# schematic.net
KiCad netlist of a schematic drawn in Altium Designer
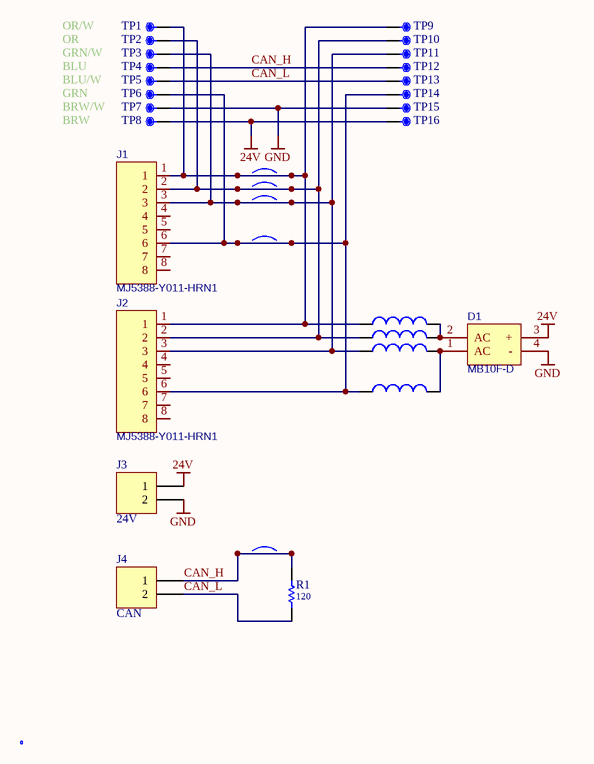
[diagram p0: schematic.SchDoc]

(export (version "E")
  (design (tool "Eeschema 10.0.6"))
  (components
    (comp (ref "D1")
      (value "MB10F-D")
      (footprint "MINIDIP_4P-L4.7-W3.8-P2.50-LS7.0-BL")
      (fields (field (name "LCSC PART NUMBER") "C908753"))
      (libsource (lib "Schlib1") (part "MB10F-D"))
    )
    (comp (ref "J1")
      (value "MJ5388-Y011-HRN1")
      (footprint "RJ45-TH_MJ5388-Y011-HRN1")
      (libsource (lib "Schlib1") (part "MJ88H-B011-HLRV1-1P_C2689153"))
    )
    (comp (ref "J2")
      (value "MJ5388-Y011-HRN1")
      (footprint "RJ45-TH_MJ5388-Y011-HRN1")
      (libsource (lib "Schlib1") (part "MJ88H-B011-HLRV1-1P_C2689153"))
    )
    (comp (ref "J3")
      (value "24V")
      (footprint "CONN_DG308-2.54-2P")
      (description "DG308-2.54-02P-14-00A(H)")
      (fields (field (name "LCSC PART NUMBER") "C699496"))
      (libsource (lib "Miscellaneous Devices") (part "CONN MOLEX HDR-M 1x4"))
    )
    (comp (ref "J4")
      (value "CAN")
      (footprint "CONN_DG308-2.54-2P")
      (description "DG308-2.54-02P-14-00A(H)")
      (fields (field (name "LCSC PART NUMBER") "C699496"))
      (libsource (lib "Miscellaneous Devices") (part "CONN MOLEX HDR-M 1x4"))
    )
    (comp (ref "L1")
      (value "BEAD")
      (footprint "L0603")
      (description "380mΩ ±25% 600Ω@100MHz 0603 Ferrite Beads")
      (fields (field (name "LCSC PART NUMBER") "C19330"))
      (libsource (lib "Miscellaneous Devices") (part "BLM18AG601SN1D"))
    )
    (comp (ref "L2")
      (value "BEAD")
      (footprint "L0603")
      (description "380mΩ ±25% 600Ω@100MHz 0603 Ferrite Beads")
      (fields (field (name "LCSC PART NUMBER") "C19330"))
      (libsource (lib "Miscellaneous Devices") (part "BLM18AG601SN1D"))
    )
    (comp (ref "L3")
      (value "BEAD")
      (footprint "L0603")
      (description "380mΩ ±25% 600Ω@100MHz 0603 Ferrite Beads")
      (fields (field (name "LCSC PART NUMBER") "C19330"))
      (libsource (lib "Miscellaneous Devices") (part "BLM18AG601SN1D"))
    )
    (comp (ref "L4")
      (value "BEAD")
      (footprint "L0603")
      (description "380mΩ ±25% 600Ω@100MHz 0603 Ferrite Beads")
      (fields (field (name "LCSC PART NUMBER") "C19330"))
      (libsource (lib "Miscellaneous Devices") (part "BLM18AG601SN1D"))
    )
    (comp (ref "LOGO1") (value "LOGO") (footprint "LOGO") (libsource (lib "Schlib1") (part "LOGO")))
    (comp (ref "R1")
      (value "120")
      (footprint "R1206")
      (description "120 1206")
      (libsource (lib "Miscellaneous Devices") (part "RES"))
    )
    (comp (ref "SB1")
      (value "Circuit Breaker")
      (footprint "JMP0402_2")
      (libsource (lib "MCD_TOOLS") (part "Circuit Breaker"))
    )
    (comp (ref "SB2")
      (value "Circuit Breaker")
      (footprint "JMP0402_2")
      (libsource (lib "MCD_TOOLS") (part "Circuit Breaker"))
    )
    (comp (ref "SB3")
      (value "Circuit Breaker")
      (footprint "JMP0402_2")
      (libsource (lib "MCD_TOOLS") (part "Circuit Breaker"))
    )
    (comp (ref "SB4")
      (value "Circuit Breaker")
      (footprint "JMP0402_2")
      (libsource (lib "MCD_TOOLS") (part "Circuit Breaker"))
    )
    (comp (ref "SB5")
      (value "Circuit Breaker")
      (footprint "JMP0402_2")
      (libsource (lib "MCD_TOOLS") (part "Circuit Breaker"))
    )
    (comp (ref "TP1")
      (value "~")
      (footprint "TP2030_SMD")
      (libsource (lib "Miscellaneous Devices") (part "TP_Dup1"))
    )
    (comp (ref "TP2")
      (value "~")
      (footprint "TP2030_SMD")
      (libsource (lib "Miscellaneous Devices") (part "TP_Dup1"))
    )
    (comp (ref "TP3")
      (value "~")
      (footprint "TP2030_SMD")
      (libsource (lib "Miscellaneous Devices") (part "TP_Dup1"))
    )
    (comp (ref "TP4")
      (value "~")
      (footprint "TP2030_SMD")
      (libsource (lib "Miscellaneous Devices") (part "TP_Dup1"))
    )
    (comp (ref "TP5")
      (value "~")
      (footprint "TP2030_SMD")
      (libsource (lib "Miscellaneous Devices") (part "TP_Dup1"))
    )
    (comp (ref "TP6")
      (value "~")
      (footprint "TP2030_SMD")
      (libsource (lib "Miscellaneous Devices") (part "TP_Dup1"))
    )
    (comp (ref "TP7")
      (value "~")
      (footprint "TP2030_SMD")
      (libsource (lib "Miscellaneous Devices") (part "TP_Dup1"))
    )
    (comp (ref "TP8")
      (value "~")
      (footprint "TP2030_SMD")
      (libsource (lib "Miscellaneous Devices") (part "TP_Dup1"))
    )
    (comp (ref "TP9")
      (value "~")
      (footprint "TP2030_SMD")
      (libsource (lib "Miscellaneous Devices") (part "TP_Dup1"))
    )
    (comp (ref "TP10")
      (value "~")
      (footprint "TP2030_SMD")
      (libsource (lib "Miscellaneous Devices") (part "TP_Dup1"))
    )
    (comp (ref "TP11")
      (value "~")
      (footprint "TP2030_SMD")
      (libsource (lib "Miscellaneous Devices") (part "TP_Dup1"))
    )
    (comp (ref "TP12")
      (value "~")
      (footprint "TP2030_SMD")
      (libsource (lib "Miscellaneous Devices") (part "TP_Dup1"))
    )
    (comp (ref "TP13")
      (value "~")
      (footprint "TP2030_SMD")
      (libsource (lib "Miscellaneous Devices") (part "TP_Dup1"))
    )
    (comp (ref "TP14")
      (value "~")
      (footprint "TP2030_SMD")
      (libsource (lib "Miscellaneous Devices") (part "TP_Dup1"))
    )
    (comp (ref "TP15")
      (value "~")
      (footprint "TP2030_SMD")
      (libsource (lib "Miscellaneous Devices") (part "TP_Dup1"))
    )
    (comp (ref "TP16")
      (value "~")
      (footprint "TP2030_SMD")
      (libsource (lib "Miscellaneous Devices") (part "TP_Dup1"))
    )
  )
  (nets
    (net (code "1") (name "/CAN_H") (class "Default")
      (node (ref "J4") (pin "1") (pinfunction "1_1") (pintype "passive"))
      (node (ref "R1") (pin "1") (pinfunction "1_1") (pintype "passive"))
      (node (ref "SB5") (pin "1") (pinfunction "1_1") (pintype "passive"))
      (node (ref "SB5") (pin "2") (pinfunction "2_2") (pintype "passive"))
      (node (ref "TP12") (pin "1") (pinfunction "1_1") (pintype "passive"))
      (node (ref "TP4") (pin "1") (pinfunction "1_1") (pintype "passive"))
    )
    (net (code "2") (name "/CAN_L") (class "Default")
      (node (ref "J4") (pin "2") (pinfunction "2_2") (pintype "passive"))
      (node (ref "R1") (pin "2") (pinfunction "2_2") (pintype "passive"))
      (node (ref "TP13") (pin "1") (pinfunction "1_1") (pintype "passive"))
      (node (ref "TP5") (pin "1") (pinfunction "1_1") (pintype "passive"))
    )
    (net (code "3") (name "24V") (class "Default")
      (node (ref "D1") (pin "3") (pinfunction "+_3") (pintype "passive"))
      (node (ref "J3") (pin "1") (pinfunction "1_1") (pintype "passive"))
      (node (ref "TP16") (pin "1") (pinfunction "1_1") (pintype "passive"))
      (node (ref "TP8") (pin "1") (pinfunction "1_1") (pintype "passive"))
    )
    (net (code "4") (name "GND") (class "Default")
      (node (ref "D1") (pin "4") (pinfunction "-_4") (pintype "passive"))
      (node (ref "J3") (pin "2") (pinfunction "2_2") (pintype "passive"))
      (node (ref "TP15") (pin "1") (pinfunction "1_1") (pintype "passive"))
      (node (ref "TP7") (pin "1") (pinfunction "1_1") (pintype "passive"))
    )
    (net (code "5") (name "Net-(D1-AC-Pad1)") (class "Default")
      (node (ref "D1") (pin "1") (pinfunction "AC_1") (pintype "passive"))
      (node (ref "L3") (pin "1") (pinfunction "1_1") (pintype "passive"))
      (node (ref "L4") (pin "1") (pinfunction "1_1") (pintype "passive"))
    )
    (net (code "6") (name "Net-(D1-AC-Pad2)") (class "Default")
      (node (ref "D1") (pin "2") (pinfunction "AC_2") (pintype "passive"))
      (node (ref "L1") (pin "1") (pinfunction "1_1") (pintype "passive"))
      (node (ref "L2") (pin "1") (pinfunction "1_1") (pintype "passive"))
    )
    (net (code "7") (name "Net-(J1-Pad1)") (class "Default")
      (node (ref "J1") (pin "1") (pinfunction "1_1") (pintype "passive"))
      (node (ref "J2") (pin "1") (pinfunction "1_1") (pintype "passive"))
      (node (ref "L1") (pin "2") (pinfunction "2_2") (pintype "passive"))
      (node (ref "SB1") (pin "1") (pinfunction "1_1") (pintype "passive"))
      (node (ref "SB1") (pin "2") (pinfunction "2_2") (pintype "passive"))
      (node (ref "TP1") (pin "1") (pinfunction "1_1") (pintype "passive"))
      (node (ref "TP9") (pin "1") (pinfunction "1_1") (pintype "passive"))
    )
    (net (code "8") (name "Net-(J1-Pad2)") (class "Default")
      (node (ref "J1") (pin "2") (pinfunction "2_2") (pintype "passive"))
      (node (ref "J2") (pin "2") (pinfunction "2_2") (pintype "passive"))
      (node (ref "L2") (pin "2") (pinfunction "2_2") (pintype "passive"))
      (node (ref "SB2") (pin "1") (pinfunction "1_1") (pintype "passive"))
      (node (ref "SB2") (pin "2") (pinfunction "2_2") (pintype "passive"))
      (node (ref "TP10") (pin "1") (pinfunction "1_1") (pintype "passive"))
      (node (ref "TP2") (pin "1") (pinfunction "1_1") (pintype "passive"))
    )
    (net (code "9") (name "Net-(J1-Pad3)") (class "Default")
      (node (ref "J1") (pin "3") (pinfunction "3_3") (pintype "passive"))
      (node (ref "J2") (pin "3") (pinfunction "3_3") (pintype "passive"))
      (node (ref "L3") (pin "2") (pinfunction "2_2") (pintype "passive"))
      (node (ref "SB3") (pin "1") (pinfunction "1_1") (pintype "passive"))
      (node (ref "SB3") (pin "2") (pinfunction "2_2") (pintype "passive"))
      (node (ref "TP11") (pin "1") (pinfunction "1_1") (pintype "passive"))
      (node (ref "TP3") (pin "1") (pinfunction "1_1") (pintype "passive"))
    )
    (net (code "10") (name "Net-(J1-Pad6)") (class "Default")
      (node (ref "J1") (pin "6") (pinfunction "6_6") (pintype "passive"))
      (node (ref "J2") (pin "6") (pinfunction "6_6") (pintype "passive"))
      (node (ref "L4") (pin "2") (pinfunction "2_2") (pintype "passive"))
      (node (ref "SB4") (pin "1") (pinfunction "1_1") (pintype "passive"))
      (node (ref "SB4") (pin "2") (pinfunction "2_2") (pintype "passive"))
      (node (ref "TP14") (pin "1") (pinfunction "1_1") (pintype "passive"))
      (node (ref "TP6") (pin "1") (pinfunction "1_1") (pintype "passive"))
    )
    (net (code "11") (name "unconnected-(J1-Pad4)") (class "Default")
      (node (ref "J1") (pin "4") (pinfunction "4_4") (pintype "passive"))
    )
    (net (code "12") (name "unconnected-(J1-Pad5)") (class "Default")
      (node (ref "J1") (pin "5") (pinfunction "5_5") (pintype "passive"))
    )
    (net (code "13") (name "unconnected-(J1-Pad7)") (class "Default")
      (node (ref "J1") (pin "7") (pinfunction "7_7") (pintype "passive"))
    )
    (net (code "14") (name "unconnected-(J1-Pad8)") (class "Default")
      (node (ref "J1") (pin "8") (pinfunction "8_8") (pintype "passive"))
    )
    (net (code "15") (name "unconnected-(J2-Pad4)") (class "Default")
      (node (ref "J2") (pin "4") (pinfunction "4_4") (pintype "passive"))
    )
    (net (code "16") (name "unconnected-(J2-Pad5)") (class "Default")
      (node (ref "J2") (pin "5") (pinfunction "5_5") (pintype "passive"))
    )
    (net (code "17") (name "unconnected-(J2-Pad7)") (class "Default")
      (node (ref "J2") (pin "7") (pinfunction "7_7") (pintype "passive"))
    )
    (net (code "18") (name "unconnected-(J2-Pad8)") (class "Default")
      (node (ref "J2") (pin "8") (pinfunction "8_8") (pintype "passive"))
    )
  )
)
